# 32u4_Drill_Shield.net
KiCad netlist of a schematic drawn in EAGLE
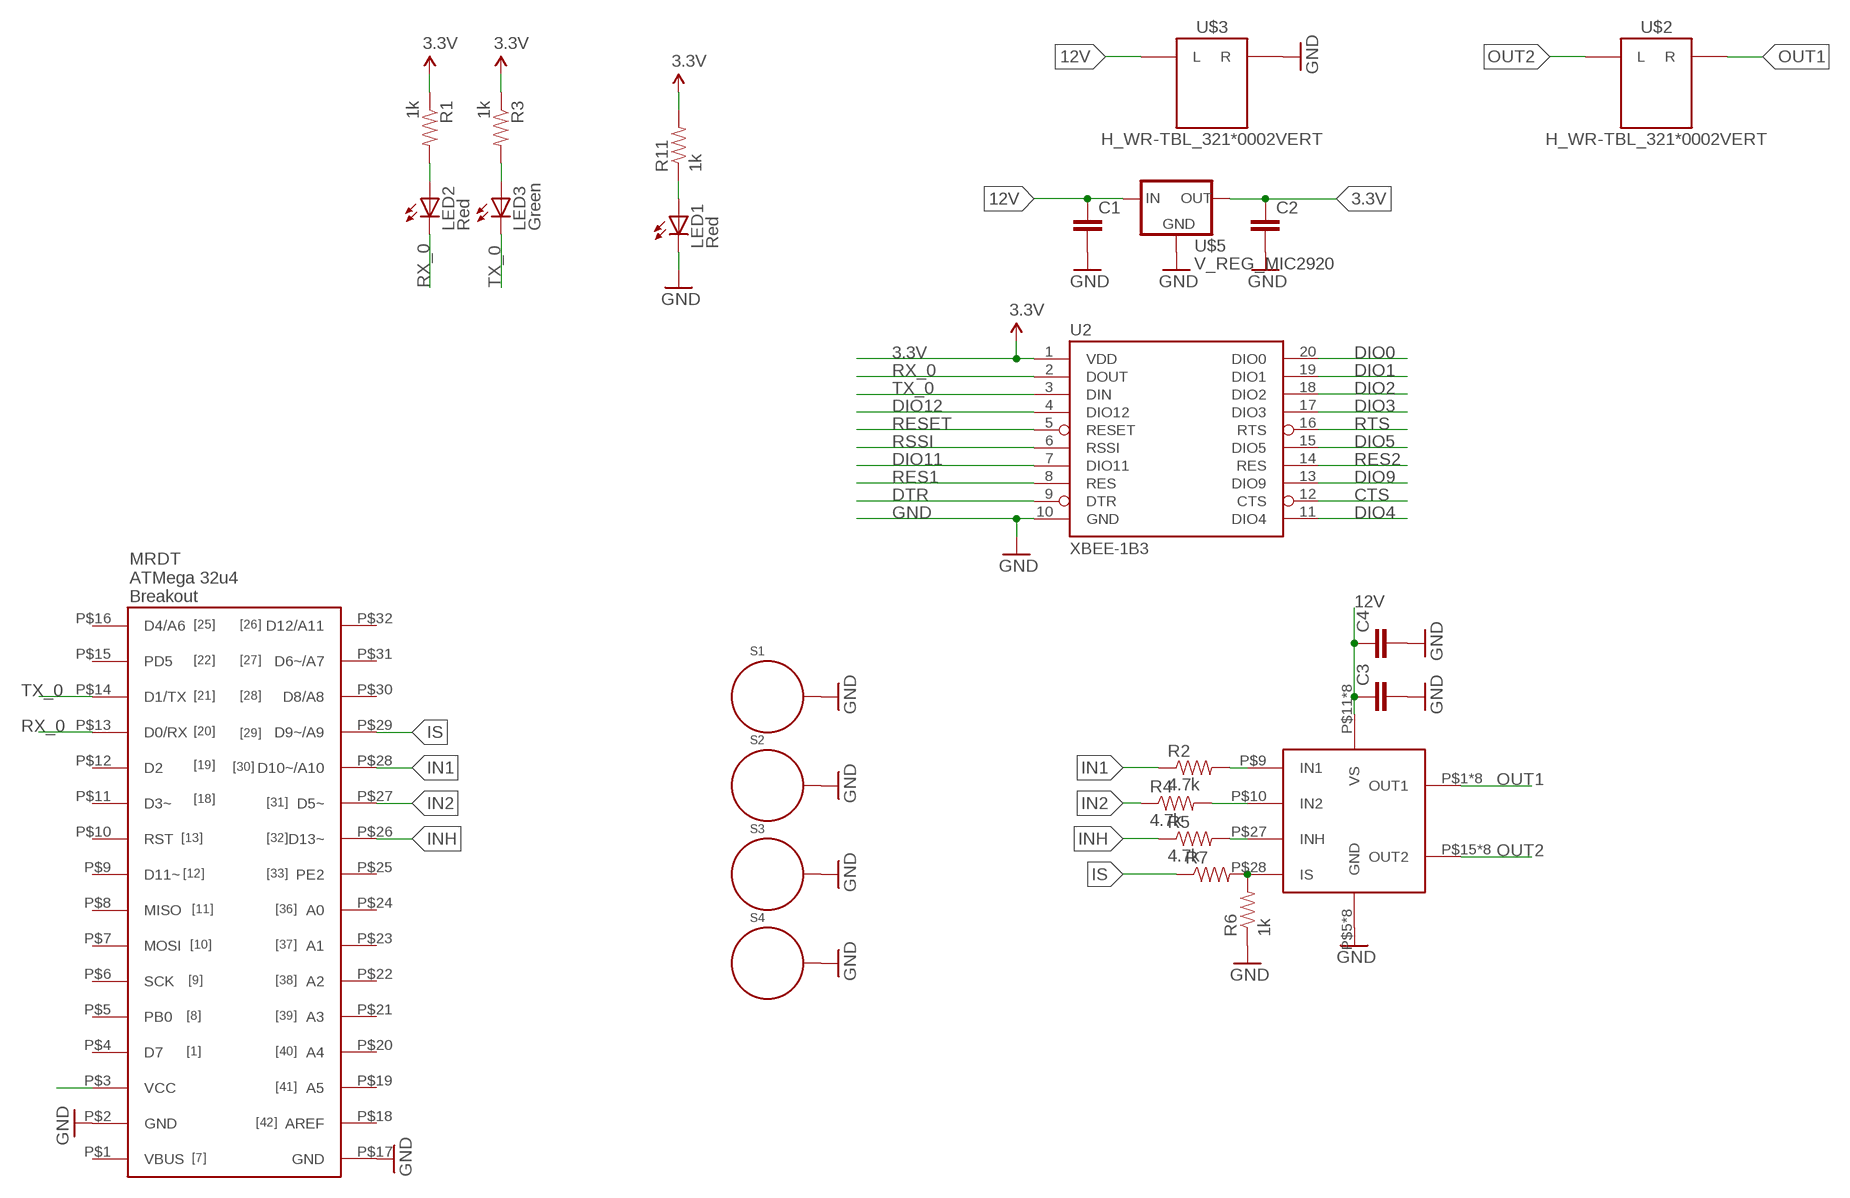
[diagram p0: schematic, sheet 1]

(export (version "E")
  (design (tool "Eeschema 10.0.6"))
  (components
    (comp (ref "C1")
      (value "CAP1206")
      (footprint "eagle-import:1206")
      (libsource (lib "eagle-import") (part "CAP1206"))
    )
    (comp (ref "C2")
      (value "CAP1206")
      (footprint "eagle-import:1206")
      (libsource (lib "eagle-import") (part "CAP1206"))
    )
    (comp (ref "C3")
      (value "CAP1206")
      (footprint "eagle-import:1206")
      (libsource (lib "eagle-import") (part "CAP1206"))
    )
    (comp (ref "C4")
      (value "CAP1206")
      (footprint "eagle-import:1206")
      (libsource (lib "eagle-import") (part "CAP1206"))
    )
    (comp (ref "LED1")
      (value "Red")
      (footprint "eagle-import:LED-0603")
      (libsource (lib "eagle-import") (part "LED0603"))
    )
    (comp (ref "LED2")
      (value "Red")
      (footprint "eagle-import:LED-0603")
      (libsource (lib "eagle-import") (part "LED0603"))
    )
    (comp (ref "LED3")
      (value "Green")
      (footprint "eagle-import:LED-0603")
      (libsource (lib "eagle-import") (part "LED0603"))
    )
    (comp (ref "R1")
      (value "1k")
      (footprint "eagle-import:1206")
      (libsource (lib "eagle-import") (part "RESISTOR1206"))
    )
    (comp (ref "R2")
      (value "4.7k")
      (footprint "eagle-import:1206")
      (libsource (lib "eagle-import") (part "RESISTOR1206"))
    )
    (comp (ref "R3")
      (value "1k")
      (footprint "eagle-import:1206")
      (libsource (lib "eagle-import") (part "RESISTOR1206"))
    )
    (comp (ref "R4")
      (value "4.7k")
      (footprint "eagle-import:1206")
      (libsource (lib "eagle-import") (part "RESISTOR1206"))
    )
    (comp (ref "R5")
      (value "4.7k")
      (footprint "eagle-import:1206")
      (libsource (lib "eagle-import") (part "RESISTOR1206"))
    )
    (comp (ref "R6")
      (value "1k")
      (footprint "eagle-import:1206")
      (libsource (lib "eagle-import") (part "RESISTOR1206"))
    )
    (comp (ref "R7")
      (value "RESISTOR1206")
      (footprint "eagle-import:1206")
      (libsource (lib "eagle-import") (part "RESISTOR1206"))
    )
    (comp (ref "R11")
      (value "1k")
      (footprint "eagle-import:1206")
      (libsource (lib "eagle-import") (part "RESISTOR1206"))
    )
    (comp (ref "S1")
      (value "STANDOFF_ELECTRICAL")
      (footprint "eagle-import:STANDOFF-ELECTRICAL")
      (libsource (lib "eagle-import") (part "STANDOFF_ELECTRICAL"))
    )
    (comp (ref "S2")
      (value "STANDOFF_ELECTRICAL")
      (footprint "eagle-import:STANDOFF-ELECTRICAL")
      (libsource (lib "eagle-import") (part "STANDOFF_ELECTRICAL"))
    )
    (comp (ref "S3")
      (value "STANDOFF_ELECTRICAL")
      (footprint "eagle-import:STANDOFF-ELECTRICAL")
      (libsource (lib "eagle-import") (part "STANDOFF_ELECTRICAL"))
    )
    (comp (ref "S4")
      (value "STANDOFF_ELECTRICAL")
      (footprint "eagle-import:STANDOFF-ELECTRICAL")
      (libsource (lib "eagle-import") (part "STANDOFF_ELECTRICAL"))
    )
    (comp (ref "U$1")
      (value "32U4_BREAKOU_SMD")
      (footprint "eagle-import:32U3_MCU_DIP_SMD")
      (libsource (lib "eagle-import") (part "32U4_BREAKOU_SMD"))
    )
    (comp (ref "U$2")
      (value "H_WR-TBL_321*0002VERT")
      (footprint "eagle-import:691321100002")
      (libsource (lib "eagle-import") (part "H_WR-TBL_3210002VERT"))
    )
    (comp (ref "U$3")
      (value "H_WR-TBL_321*0002VERT")
      (footprint "eagle-import:691321100002")
      (libsource (lib "eagle-import") (part "H_WR-TBL_3210002VERT"))
    )
    (comp (ref "U$4")
      (value "BTM7752G")
      (footprint "eagle-import:BTM7752G")
      (libsource (lib "eagle-import") (part "BTM7752G"))
    )
    (comp (ref "U$5")
      (value "V_REG_MIC2920")
      (footprint "eagle-import:SOT223")
      (libsource (lib "eagle-import") (part "V_REG_MIC2920"))
    )
    (comp (ref "U2")
      (value "XBEE-1B3")
      (footprint "eagle-import:XBEE-SMD")
      (libsource (lib "eagle-import") (part "XBEE-1B3"))
    )
  )
  (nets
    (net (code "1") (name "/CTS") (class "Default")
      (node (ref "U2") (pin "12") (pinfunction "CTS_12") (pintype "output"))
    )
    (net (code "2") (name "/DIO0") (class "Default")
      (node (ref "U2") (pin "20") (pinfunction "DIO0_20") (pintype "bidirectional"))
    )
    (net (code "3") (name "/DIO1") (class "Default")
      (node (ref "U2") (pin "19") (pinfunction "DIO1_19") (pintype "bidirectional"))
    )
    (net (code "4") (name "/DIO2") (class "Default")
      (node (ref "U2") (pin "18") (pinfunction "DIO2_18") (pintype "bidirectional"))
    )
    (net (code "5") (name "/DIO3") (class "Default")
      (node (ref "U2") (pin "17") (pinfunction "DIO3_17") (pintype "bidirectional"))
    )
    (net (code "6") (name "/DIO4") (class "Default")
      (node (ref "U2") (pin "11") (pinfunction "DIO4_11") (pintype "bidirectional"))
    )
    (net (code "7") (name "/DIO5") (class "Default")
      (node (ref "U2") (pin "15") (pinfunction "DIO5_15") (pintype "bidirectional"))
    )
    (net (code "8") (name "/DIO9") (class "Default")
      (node (ref "U2") (pin "13") (pinfunction "DIO9_13") (pintype "bidirectional"))
    )
    (net (code "9") (name "/DIO11") (class "Default")
      (node (ref "U2") (pin "7") (pinfunction "DIO11_7") (pintype "bidirectional"))
    )
    (net (code "10") (name "/DIO12") (class "Default")
      (node (ref "U2") (pin "4") (pinfunction "DIO12_4") (pintype "bidirectional"))
    )
    (net (code "11") (name "/DTR") (class "Default")
      (node (ref "U2") (pin "9") (pinfunction "DTR_9") (pintype "bidirectional"))
    )
    (net (code "12") (name "/RES1") (class "Default")
      (node (ref "U2") (pin "8") (pinfunction "RES_8") (pintype "bidirectional"))
    )
    (net (code "13") (name "/RES2") (class "Default")
      (node (ref "U2") (pin "14") (pinfunction "RES_14") (pintype "bidirectional"))
    )
    (net (code "14") (name "/RESET") (class "Default")
      (node (ref "U2") (pin "5") (pinfunction "RESET_5") (pintype "input"))
    )
    (net (code "15") (name "/RSSI") (class "Default")
      (node (ref "U2") (pin "6") (pinfunction "RSSI_6") (pintype "bidirectional"))
    )
    (net (code "16") (name "/RTS") (class "Default")
      (node (ref "U2") (pin "16") (pinfunction "RTS_16") (pintype "input"))
    )
    (net (code "17") (name "/RX_0") (class "Default")
      (node (ref "LED2") (pin "C") (pinfunction "C_C") (pintype "passive"))
      (node (ref "U$1") (pin "P$13") (pinfunction "D0/RX_P$13") (pintype "bidirectional"))
      (node (ref "U2") (pin "2") (pinfunction "DOUT_2") (pintype "output"))
    )
    (net (code "18") (name "/TX_0") (class "Default")
      (node (ref "LED3") (pin "C") (pinfunction "C_C") (pintype "passive"))
      (node (ref "U$1") (pin "P$14") (pinfunction "D1/TX_P$14") (pintype "bidirectional"))
      (node (ref "U2") (pin "3") (pinfunction "DIN_3") (pintype "input"))
    )
    (net (code "19") (name "3.3V") (class "Default")
      (node (ref "C2") (pin "1") (pinfunction "1_1") (pintype "passive"))
      (node (ref "R1") (pin "1") (pinfunction "1_1") (pintype "passive"))
      (node (ref "R11") (pin "2") (pinfunction "2_2") (pintype "passive"))
      (node (ref "R3") (pin "1") (pinfunction "1_1") (pintype "passive"))
      (node (ref "U$1") (pin "P$3") (pinfunction "VCC_P$3") (pintype "bidirectional"))
      (node (ref "U$5") (pin "3") (pinfunction "OUT_3") (pintype "output"))
      (node (ref "U2") (pin "1") (pinfunction "VDD_1") (pintype "power_in"))
    )
    (net (code "20") (name "12V") (class "Default")
      (node (ref "C1") (pin "1") (pinfunction "1_1") (pintype "passive"))
      (node (ref "C3") (pin "1") (pinfunction "1_1") (pintype "passive"))
      (node (ref "C4") (pin "1") (pinfunction "1_1") (pintype "passive"))
      (node (ref "U$3") (pin "L") (pinfunction "L_L") (pintype "bidirectional"))
      (node (ref "U$4") (pin "P$11") (pinfunction "VS_P$11") (pintype "bidirectional"))
      (node (ref "U$4") (pin "P$12") (pinfunction "VS_P$12") (pintype "bidirectional"))
      (node (ref "U$4") (pin "P$13") (pinfunction "VS_P$13") (pintype "bidirectional"))
      (node (ref "U$4") (pin "P$14") (pinfunction "VS_P$14") (pintype "bidirectional"))
      (node (ref "U$4") (pin "P$29") (pinfunction "VS_P$29") (pintype "bidirectional"))
      (node (ref "U$4") (pin "P$30") (pinfunction "VS_P$30") (pintype "bidirectional"))
      (node (ref "U$4") (pin "P$31") (pinfunction "VS_P$31") (pintype "bidirectional"))
      (node (ref "U$4") (pin "P$32") (pinfunction "VS_P$32") (pintype "bidirectional"))
      (node (ref "U$5") (pin "1") (pinfunction "IN_1") (pintype "input"))
    )
    (net (code "21") (name "GND") (class "Default")
      (node (ref "C1") (pin "2") (pinfunction "2_2") (pintype "passive"))
      (node (ref "C2") (pin "2") (pinfunction "2_2") (pintype "passive"))
      (node (ref "C3") (pin "2") (pinfunction "2_2") (pintype "passive"))
      (node (ref "C4") (pin "2") (pinfunction "2_2") (pintype "passive"))
      (node (ref "LED1") (pin "C") (pinfunction "C_C") (pintype "passive"))
      (node (ref "R6") (pin "1") (pinfunction "1_1") (pintype "passive"))
      (node (ref "S1") (pin "P1") (pinfunction "P$1_P1") (pintype "bidirectional"))
      (node (ref "S2") (pin "P1") (pinfunction "P$1_P1") (pintype "bidirectional"))
      (node (ref "S3") (pin "P1") (pinfunction "P$1_P1") (pintype "bidirectional"))
      (node (ref "S4") (pin "P1") (pinfunction "P$1_P1") (pintype "bidirectional"))
      (node (ref "U$1") (pin "P$17") (pinfunction "GND_P$17") (pintype "bidirectional"))
      (node (ref "U$1") (pin "P$2") (pinfunction "GND_P$2") (pintype "bidirectional"))
      (node (ref "U$3") (pin "R") (pinfunction "R_R") (pintype "bidirectional"))
      (node (ref "U$4") (pin "P$23") (pinfunction "GND_P$23") (pintype "bidirectional"))
      (node (ref "U$4") (pin "P$24") (pinfunction "GND_P$24") (pintype "bidirectional"))
      (node (ref "U$4") (pin "P$25") (pinfunction "GND_P$25") (pintype "bidirectional"))
      (node (ref "U$4") (pin "P$26") (pinfunction "GND_P$26") (pintype "bidirectional"))
      (node (ref "U$4") (pin "P$5") (pinfunction "GND_P$5") (pintype "bidirectional"))
      (node (ref "U$4") (pin "P$6") (pinfunction "GND_P$6") (pintype "bidirectional"))
      (node (ref "U$4") (pin "P$7") (pinfunction "GND_P$7") (pintype "bidirectional"))
      (node (ref "U$4") (pin "P$8") (pinfunction "GND_P$8") (pintype "bidirectional"))
      (node (ref "U$5") (pin "2") (pinfunction "GND_2") (pintype "input"))
      (node (ref "U$5") (pin "4") (pinfunction "GND_4") (pintype "input"))
      (node (ref "U2") (pin "10") (pinfunction "GND_10") (pintype "power_in"))
    )
    (net (code "22") (name "IN1") (class "Default")
      (node (ref "R2") (pin "1") (pinfunction "1_1") (pintype "passive"))
      (node (ref "U$1") (pin "P$28") (pinfunction "D10~{/A10}_P$28") (pintype "bidirectional"))
    )
    (net (code "23") (name "IN2") (class "Default")
      (node (ref "R4") (pin "1") (pinfunction "1_1") (pintype "passive"))
      (node (ref "U$1") (pin "P$27") (pinfunction "D5~{}_P$27") (pintype "bidirectional"))
    )
    (net (code "24") (name "INH") (class "Default")
      (node (ref "R5") (pin "1") (pinfunction "1_1") (pintype "passive"))
      (node (ref "U$1") (pin "P$26") (pinfunction "D13~{}_P$26") (pintype "bidirectional"))
    )
    (net (code "25") (name "IS") (class "Default")
      (node (ref "R7") (pin "1") (pinfunction "1_1") (pintype "passive"))
      (node (ref "U$1") (pin "P$29") (pinfunction "D9~{/A9}_P$29") (pintype "bidirectional"))
    )
    (net (code "26") (name "Net-(LED1-PadA)") (class "Default")
      (node (ref "LED1") (pin "A") (pinfunction "A_A") (pintype "passive"))
      (node (ref "R11") (pin "1") (pinfunction "1_1") (pintype "passive"))
    )
    (net (code "27") (name "Net-(LED2-PadA)") (class "Default")
      (node (ref "LED2") (pin "A") (pinfunction "A_A") (pintype "passive"))
      (node (ref "R1") (pin "2") (pinfunction "2_2") (pintype "passive"))
    )
    (net (code "28") (name "Net-(LED3-PadA)") (class "Default")
      (node (ref "LED3") (pin "A") (pinfunction "A_A") (pintype "passive"))
      (node (ref "R3") (pin "2") (pinfunction "2_2") (pintype "passive"))
    )
    (net (code "29") (name "Net-(U$4-IN1)") (class "Default")
      (node (ref "R2") (pin "2") (pinfunction "2_2") (pintype "passive"))
      (node (ref "U$4") (pin "P$9") (pinfunction "IN1_P$9") (pintype "bidirectional"))
    )
    (net (code "30") (name "Net-(U$4-IN2)") (class "Default")
      (node (ref "R4") (pin "2") (pinfunction "2_2") (pintype "passive"))
      (node (ref "U$4") (pin "P$10") (pinfunction "IN2_P$10") (pintype "bidirectional"))
    )
    (net (code "31") (name "Net-(U$4-INH)") (class "Default")
      (node (ref "R5") (pin "2") (pinfunction "2_2") (pintype "passive"))
      (node (ref "U$4") (pin "P$27") (pinfunction "INH_P$27") (pintype "bidirectional"))
    )
    (net (code "32") (name "Net-(U$4-IS)") (class "Default")
      (node (ref "R6") (pin "2") (pinfunction "2_2") (pintype "passive"))
      (node (ref "R7") (pin "2") (pinfunction "2_2") (pintype "passive"))
      (node (ref "U$4") (pin "P$28") (pinfunction "IS_P$28") (pintype "bidirectional"))
    )
    (net (code "33") (name "OUT1") (class "Default")
      (node (ref "U$2") (pin "R") (pinfunction "R_R") (pintype "bidirectional"))
      (node (ref "U$4") (pin "P$1") (pinfunction "OUT1_P$1") (pintype "bidirectional"))
      (node (ref "U$4") (pin "P$2") (pinfunction "OUT1_P$2") (pintype "bidirectional"))
      (node (ref "U$4") (pin "P$3") (pinfunction "OUT1_P$3") (pintype "bidirectional"))
      (node (ref "U$4") (pin "P$33") (pinfunction "OUT1_P$33") (pintype "bidirectional"))
      (node (ref "U$4") (pin "P$34") (pinfunction "OUT1_P$34") (pintype "bidirectional"))
      (node (ref "U$4") (pin "P$35") (pinfunction "OUT1_P$35") (pintype "bidirectional"))
      (node (ref "U$4") (pin "P$36") (pinfunction "OUT1_P$36") (pintype "bidirectional"))
      (node (ref "U$4") (pin "P$4") (pinfunction "OUT1_P$4") (pintype "bidirectional"))
    )
    (net (code "34") (name "OUT2") (class "Default")
      (node (ref "U$2") (pin "L") (pinfunction "L_L") (pintype "bidirectional"))
      (node (ref "U$4") (pin "P$15") (pinfunction "OUT2_P$15") (pintype "bidirectional"))
      (node (ref "U$4") (pin "P$16") (pinfunction "OUT2_P$16") (pintype "bidirectional"))
      (node (ref "U$4") (pin "P$17") (pinfunction "OUT2_P$17") (pintype "bidirectional"))
      (node (ref "U$4") (pin "P$18") (pinfunction "OUT2_P$18") (pintype "bidirectional"))
      (node (ref "U$4") (pin "P$19") (pinfunction "OUT2_P$19") (pintype "bidirectional"))
      (node (ref "U$4") (pin "P$20") (pinfunction "OUT2_P$20") (pintype "bidirectional"))
      (node (ref "U$4") (pin "P$21") (pinfunction "OUT2_P$21") (pintype "bidirectional"))
      (node (ref "U$4") (pin "P$22") (pinfunction "OUT2_P$22") (pintype "bidirectional"))
    )
    (net (code "35") (name "unconnected-(U$1-A0-PadP$24)") (class "Default")
      (node (ref "U$1") (pin "P$24") (pinfunction "A0_P$24") (pintype "bidirectional"))
    )
    (net (code "36") (name "unconnected-(U$1-A1-PadP$23)") (class "Default")
      (node (ref "U$1") (pin "P$23") (pinfunction "A1_P$23") (pintype "bidirectional"))
    )
    (net (code "37") (name "unconnected-(U$1-A2-PadP$22)") (class "Default")
      (node (ref "U$1") (pin "P$22") (pinfunction "A2_P$22") (pintype "bidirectional"))
    )
    (net (code "38") (name "unconnected-(U$1-A3-PadP$21)") (class "Default")
      (node (ref "U$1") (pin "P$21") (pinfunction "A3_P$21") (pintype "bidirectional"))
    )
    (net (code "39") (name "unconnected-(U$1-A4-PadP$20)") (class "Default")
      (node (ref "U$1") (pin "P$20") (pinfunction "A4_P$20") (pintype "bidirectional"))
    )
    (net (code "40") (name "unconnected-(U$1-A5-PadP$19)") (class "Default")
      (node (ref "U$1") (pin "P$19") (pinfunction "A5_P$19") (pintype "bidirectional"))
    )
    (net (code "41") (name "unconnected-(U$1-AREF-PadP$18)") (class "Default")
      (node (ref "U$1") (pin "P$18") (pinfunction "AREF_P$18") (pintype "bidirectional"))
    )
    (net (code "42") (name "unconnected-(U$1-D2-PadP$12)") (class "Default")
      (node (ref "U$1") (pin "P$12") (pinfunction "D2_P$12") (pintype "bidirectional"))
    )
    (net (code "43") (name "unconnected-(U$1-D3~{}-PadP$11)") (class "Default")
      (node (ref "U$1") (pin "P$11") (pinfunction "D3~{}_P$11") (pintype "bidirectional"))
    )
    (net (code "44") (name "unconnected-(U$1-D4{slash}A6-PadP$16)") (class "Default")
      (node (ref "U$1") (pin "P$16") (pinfunction "D4/A6_P$16") (pintype "bidirectional"))
    )
    (net (code "45") (name "unconnected-(U$1-D6~{{slash}A7}-PadP$31)") (class "Default")
      (node (ref "U$1") (pin "P$31") (pinfunction "D6~{/A7}_P$31") (pintype "bidirectional"))
    )
    (net (code "46") (name "unconnected-(U$1-D7-PadP$4)") (class "Default")
      (node (ref "U$1") (pin "P$4") (pinfunction "D7_P$4") (pintype "bidirectional"))
    )
    (net (code "47") (name "unconnected-(U$1-D8{slash}A8-PadP$30)") (class "Default")
      (node (ref "U$1") (pin "P$30") (pinfunction "D8/A8_P$30") (pintype "bidirectional"))
    )
    (net (code "48") (name "unconnected-(U$1-D11~{}-PadP$9)") (class "Default")
      (node (ref "U$1") (pin "P$9") (pinfunction "D11~{}_P$9") (pintype "bidirectional"))
    )
    (net (code "49") (name "unconnected-(U$1-D12{slash}A11-PadP$32)") (class "Default")
      (node (ref "U$1") (pin "P$32") (pinfunction "D12/A11_P$32") (pintype "bidirectional"))
    )
    (net (code "50") (name "unconnected-(U$1-MISO-PadP$8)") (class "Default")
      (node (ref "U$1") (pin "P$8") (pinfunction "MISO_P$8") (pintype "bidirectional"))
    )
    (net (code "51") (name "unconnected-(U$1-MOSI-PadP$7)") (class "Default")
      (node (ref "U$1") (pin "P$7") (pinfunction "MOSI_P$7") (pintype "bidirectional"))
    )
    (net (code "52") (name "unconnected-(U$1-PB0-PadP$5)") (class "Default")
      (node (ref "U$1") (pin "P$5") (pinfunction "PB0_P$5") (pintype "bidirectional"))
    )
    (net (code "53") (name "unconnected-(U$1-PD5-PadP$15)") (class "Default")
      (node (ref "U$1") (pin "P$15") (pinfunction "PD5_P$15") (pintype "bidirectional"))
    )
    (net (code "54") (name "unconnected-(U$1-PE2-PadP$25)") (class "Default")
      (node (ref "U$1") (pin "P$25") (pinfunction "PE2_P$25") (pintype "bidirectional"))
    )
    (net (code "55") (name "unconnected-(U$1-RST-PadP$10)") (class "Default")
      (node (ref "U$1") (pin "P$10") (pinfunction "RST_P$10") (pintype "bidirectional"))
    )
    (net (code "56") (name "unconnected-(U$1-SCK-PadP$6)") (class "Default")
      (node (ref "U$1") (pin "P$6") (pinfunction "SCK_P$6") (pintype "bidirectional"))
    )
    (net (code "57") (name "unconnected-(U$1-VBUS-PadP$1)") (class "Default")
      (node (ref "U$1") (pin "P$1") (pinfunction "VBUS_P$1") (pintype "bidirectional"))
    )
  )
)
